# 533_4POV.net
KiCad netlist of a schematic drawn in Altium Designer
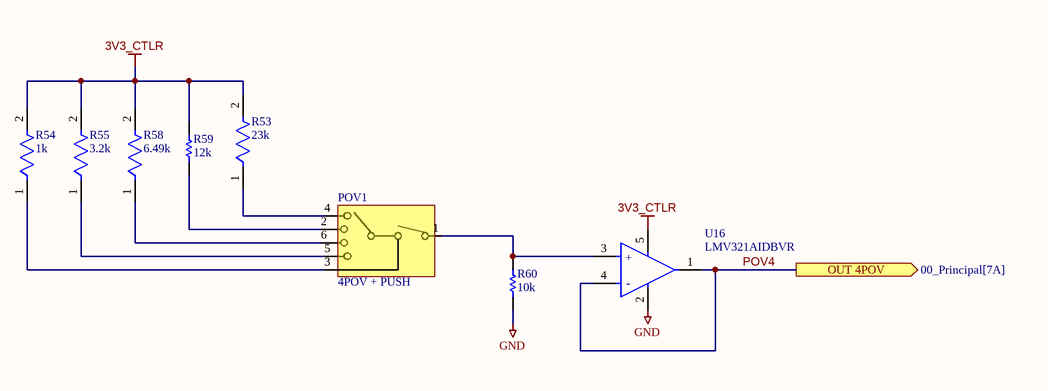
[diagram p0: 533_4POV.SchDoc]

(export (version "E")
  (design (tool "Eeschema 10.0.6"))
  (components
    (comp (ref "POV1")
      (value "4POV + PUSH")
      (footprint "TSSJ 30")
      (description "SWITCH NAVIGATION 20MA 15V")
      (libsource (lib "Esquemas") (part "TSSJ 30"))
    )
    (comp (ref "R53")
      (value "23k")
      (footprint "FP-AC0402-MFG")
      (description "RES 23.2kΩ ±1% 0.063W 0402")
      (fields (field (name "TOLERANCE") "1%"))
      (libsource (lib "Altium Content Vault") (part "1029c3af85768c4190bb7ad29bc67b5"))
    )
    (comp (ref "R54")
      (value "1k")
      (footprint "FP-MCS0402-IPC_B")
      (description "RES SMD 1.2K OHM 1% 1/10W 0402")
      (fields (field (name "TOLERANCE") "0.1%"))
      (libsource (lib "Altium Content Vault") (part "1029c3af85768c4190bb7ad29bc67b5"))
    )
    (comp (ref "R55")
      (value "3.2k")
      (footprint "FP-RN73R1E-IPC_A")
      (description "3.2kΩ ±0.1% 0.063W, 1/16W Chip Resistor 0402 (1005 Metric) Moisture Resistant Thin Film")
      (libsource (lib "Altium Content Vault") (part "1029c3af85768c4190bb7ad29bc67b5"))
    )
    (comp (ref "R58")
      (value "6.49k")
      (footprint "FP-MCS0402-IPC_A")
      (description "RES SMD 1.2K OHM 1% 1/10W 0402")
      (fields (field (name "TOLERANCE") "1%"))
      (libsource (lib "Altium Content Vault") (part "1029c3af85768c4190bb7ad29bc67b5"))
    )
    (comp (ref "R59")
      (value "12k")
      (footprint "RESC0402(1005)_M")
      (description "12K 0.063W 5% 0402 (1005 Metric)  SMD")
      (fields (field (name "TOLERANCE") "5 %") (field (name "POWER") "0.063 W"))
      (libsource (lib "Altium Content Vault") (part "RES"))
    )
    (comp (ref "R60")
      (value "10k")
      (footprint "RESC1005X40X25ML05T05")
      (fields (field (name "MANUFACTURER") "Panasonic") (field (name "PART NUMBER") "ERJ-2RHD1002X"))
      (libsource (lib "Altium Content Vault") (part "RES"))
    )
    (comp (ref "U16")
      (value "LMV321AIDBVR")
      (footprint "FP-DBV0005A-MFG")
      (description "IC OPAMP GP 1 CIRCUIT SOT23-5")
      (libsource (lib "Altium Content Vault") (part "1dcd28e651784f0a5a8ed6f8452eeff"))
    )
  )
  (nets
    (net (code "1") (name "/POV4") (class "Default")
      (node (ref "U16") (pin "1") (pinfunction "OUT_1") (pintype "passive"))
      (node (ref "U16") (pin "4") (pinfunction "-IN_4") (pintype "tri_state"))
    )
    (net (code "2") (name "3V3_CTLR") (class "Default")
      (node (ref "R53") (pin "2") (pinfunction "2_2") (pintype "passive"))
      (node (ref "R54") (pin "2") (pinfunction "2_2") (pintype "passive"))
      (node (ref "R55") (pin "2") (pinfunction "2_2") (pintype "passive"))
      (node (ref "R58") (pin "2") (pinfunction "2_2") (pintype "passive"))
      (node (ref "R59") (pin "2") (pinfunction "2_2") (pintype "passive"))
      (node (ref "U16") (pin "5") (pinfunction "V+_5") (pintype "passive"))
    )
    (net (code "3") (name "GND") (class "Default")
      (node (ref "R60") (pin "1") (pinfunction "1_1") (pintype "passive"))
      (node (ref "U16") (pin "2") (pinfunction "V-_2") (pintype "passive"))
    )
    (net (code "4") (name "Net-(POV1-4)") (class "Default")
      (node (ref "POV1") (pin "3") (pinfunction "4_3") (pintype "passive"))
      (node (ref "R54") (pin "1") (pinfunction "1_1") (pintype "passive"))
    )
    (net (code "5") (name "Net-(POV1-COM)") (class "Default")
      (node (ref "POV1") (pin "1") (pinfunction "COM_1") (pintype "passive"))
      (node (ref "R60") (pin "2") (pinfunction "2_2") (pintype "passive"))
      (node (ref "U16") (pin "3") (pinfunction "+IN_3") (pintype "tri_state"))
    )
    (net (code "6") (name "Net-(POV1-DIRA)") (class "Default")
      (node (ref "POV1") (pin "4") (pinfunction "DIRA_4") (pintype "passive"))
      (node (ref "R53") (pin "1") (pinfunction "1_1") (pintype "passive"))
    )
    (net (code "7") (name "Net-(POV1-DIRB)") (class "Default")
      (node (ref "POV1") (pin "2") (pinfunction "DIRB_2") (pintype "passive"))
      (node (ref "R59") (pin "1") (pinfunction "1_1") (pintype "passive"))
    )
    (net (code "8") (name "Net-(POV1-DIRC)") (class "Default")
      (node (ref "POV1") (pin "6") (pinfunction "DIRC_6") (pintype "passive"))
      (node (ref "R58") (pin "1") (pinfunction "1_1") (pintype "passive"))
    )
    (net (code "9") (name "Net-(POV1-DIRD)") (class "Default")
      (node (ref "POV1") (pin "5") (pinfunction "DIRD_5") (pintype "passive"))
      (node (ref "R55") (pin "1") (pinfunction "1_1") (pintype "passive"))
    )
  )
)
